# CH32V002F4U.net
KiCad netlist of a schematic drawn in Altium Designer
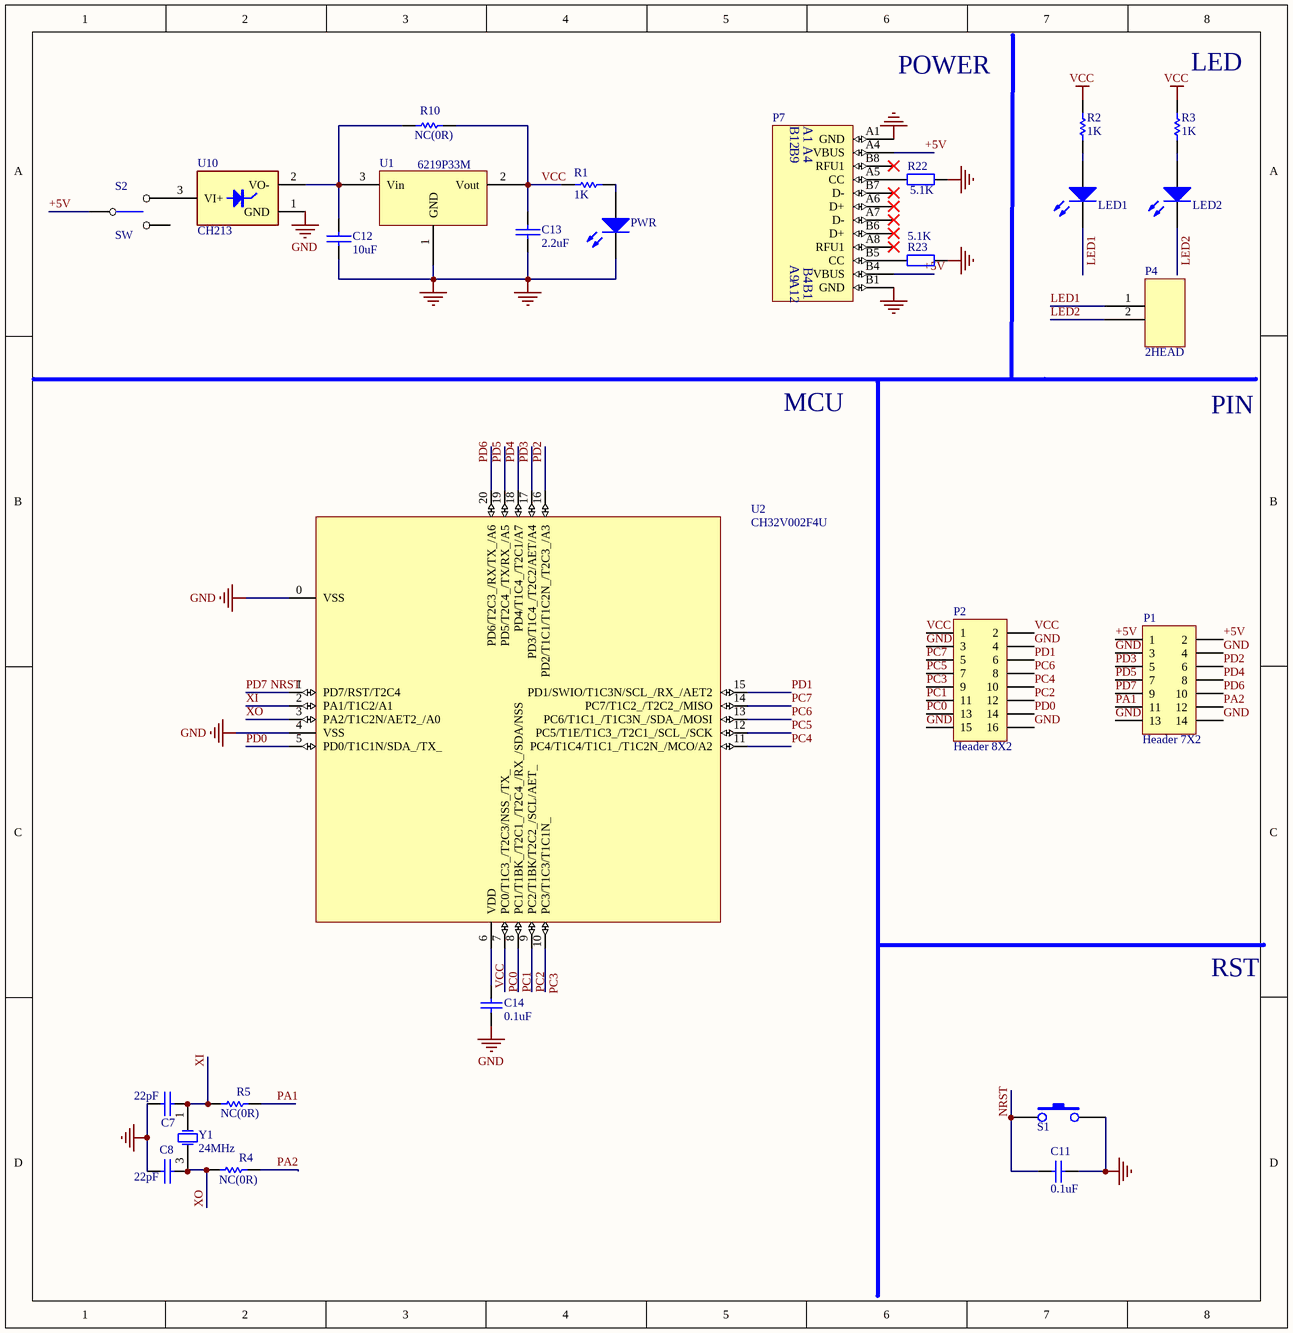
[diagram p0: CH32V002F4U.SchDoc]

(export (version "E")
  (design (tool "Eeschema 10.0.6"))
  (components
    (comp (ref "C7")
      (value "22pF")
      (footprint "0402_C")
      (description "Capacitor")
      (libsource (lib "*") (part "CAP"))
    )
    (comp (ref "C8")
      (value "22pF")
      (footprint "0402_C")
      (description "Capacitor")
      (libsource (lib "*") (part "CAP"))
    )
    (comp (ref "C11")
      (value "0.1uF")
      (footprint "0402_C")
      (description "Capacitor")
      (fields (field (name "PUBLISHER") "Altium Limited"))
      (libsource (lib "*") (part "Cap"))
    )
    (comp (ref "C12")
      (value "10uF")
      (footprint "0603_C")
      (description "Capacitor")
      (libsource (lib "wch_sch_others") (part "CAP"))
    )
    (comp (ref "C13")
      (value "2.2uF")
      (footprint "0402_C")
      (description "Capacitor")
      (libsource (lib "wch_sch_others") (part "CAP"))
    )
    (comp (ref "C14")
      (value "0.1uF")
      (footprint "0603_C")
      (description "Capacitor")
      (fields (field (name "PUBLISHER") "Altium Limited"))
      (libsource (lib "*") (part "Cap"))
    )
    (comp (ref "LED1")
      (value "LED1   blue")
      (footprint "0603+")
      (description "Typical INFRARED GaAs LED")
      (fields (field (name "PUBLISHER") "Altium Limited"))
      (libsource (lib "") (part "LED0_1"))
    )
    (comp (ref "LED2")
      (value "LED2  blue")
      (footprint "0603+")
      (description "Typical INFRARED GaAs LED")
      (fields (field (name "PUBLISHER") "Altium Limited"))
      (libsource (lib "") (part "LED0_1"))
    )
    (comp (ref "P1")
      (value "Header 7X2")
      (footprint "HDR2X7")
      (description "Header, 7-Pin, Dual row")
      (fields (field (name "PUBLISHER") "Altium Limited"))
      (libsource (lib "Miscellaneous Connectors") (part "Header 7X2"))
    )
    (comp (ref "P2")
      (value "Header 8X2")
      (footprint "HDR2X8")
      (description "Header, 8-Pin, Dual row")
      (fields (field (name "PUBLISHER") "Altium Limited"))
      (libsource (lib "Miscellaneous Connectors") (part "Header 8X2"))
    )
    (comp (ref "P4") (value "2HEAD") (footprint "SIP2-2.54mm") (libsource (lib "*") (part "2HEAD")))
    (comp (ref "P7")
      (value "TYPE-C")
      (footprint "TYPE-C-Receptacle-2.0")
      (libsource (lib "*") (part "TYPE-C1"))
    )
    (comp (ref "PWR")
      (value "POWER  red")
      (footprint "0603+")
      (description "Typical INFRARED GaAs LED")
      (fields (field (name "PUBLISHER") "Altium Limited"))
      (libsource (lib "*") (part "LED0"))
    )
    (comp (ref "R1")
      (value "1K")
      (footprint "0402")
      (description "Semiconductor Resistor")
      (fields (field (name "PUBLISHER") "Altium Limited"))
      (libsource (lib "*") (part "Res Semi"))
    )
    (comp (ref "R2")
      (value "1K")
      (footprint "0402")
      (description "Semiconductor Resistor")
      (fields (field (name "PUBLISHER") "Altium Limited"))
      (libsource (lib "*") (part "Res Semi"))
    )
    (comp (ref "R3")
      (value "1K")
      (footprint "0402")
      (description "Semiconductor Resistor")
      (fields (field (name "PUBLISHER") "Altium Limited"))
      (libsource (lib "*") (part "Res Semi"))
    )
    (comp (ref "R4")
      (value "NC(0R)")
      (footprint "0402")
      (description "Semiconductor Resistor")
      (fields (field (name "Comment") "0R") (field (name "PUBLISHER") "Altium Limited"))
      (libsource (lib "*") (part "Res Semi"))
    )
    (comp (ref "R5")
      (value "NC(0R)")
      (footprint "0402")
      (description "Semiconductor Resistor")
      (fields (field (name "Comment") "0R") (field (name "PUBLISHER") "Altium Limited"))
      (libsource (lib "*") (part "Res Semi"))
    )
    (comp (ref "R10")
      (value "NC(0R)")
      (footprint "0402")
      (description "Semiconductor Resistor")
      (fields (field (name "Comment") "0R") (field (name "PUBLISHER") "Altium Limited"))
      (libsource (lib "*") (part "Res Semi"))
    )
    (comp (ref "R22")
      (value "5.1K")
      (footprint "0402")
      (description "Resistor")
      (libsource (lib "Miscellaneous Devices") (part "Res2"))
    )
    (comp (ref "R23")
      (value "5.1K")
      (footprint "0402")
      (description "Resistor")
      (libsource (lib "Miscellaneous Devices") (part "Res2"))
    )
    (comp (ref "S1") (value "NRST") (footprint "SMD_6.1x3.65x2.5mm-KEY") (libsource (lib "*") (part "KEY")))
    (comp (ref "S2") (value "SW") (footprint "SW1") (libsource (lib "*") (part "SW")))
    (comp (ref "U1")
      (value "6219P33M")
      (footprint "SOT-23")
      (libsource (lib "wch_sch_others") (part "6219P33M"))
    )
    (comp (ref "U2")
      (value "CH32V002F4U")
      (footprint "QFN20_3X3")
      (description "RISC-V MCU, 48MHz, ADC/UART/I2C/SPI")
      (libsource (lib "DHXXXSCH") (part "CH32V002F4U6"))
    )
    (comp (ref "U10")
      (value "CH213")
      (footprint "SOT-23-3")
      (description "Ideal Diode 5V*1A")
      (libsource (lib "CHXXX") (part "CH213E"))
    )
    (comp (ref "Y1")
      (value "24MHz")
      (footprint "XT3225")
      (description "Crystal Oscillator")
      (fields (field (name "PUBLISHER") "Altium Limited"))
      (libsource (lib "*") (part "XTAL"))
    )
  )
  (nets
    (net (code "1") (name "/+5V") (class "Default")
      (node (ref "P1") (pin "1") (pinfunction "1_1") (pintype "passive"))
      (node (ref "P1") (pin "2") (pinfunction "2_2") (pintype "passive"))
      (node (ref "P7") (pin "A4") (pinfunction "VBUS_A4") (pintype "bidirectional"))
      (node (ref "P7") (pin "B4") (pinfunction "VBUS_B4") (pintype "bidirectional"))
      (node (ref "S2") (pin "1") (pinfunction "1_1") (pintype "passive"))
    )
    (net (code "2") (name "/LED1") (class "Default")
      (node (ref "LED1") (pin "2") (pinfunction "K_2") (pintype "passive"))
      (node (ref "P4") (pin "1") (pintype "passive"))
    )
    (net (code "3") (name "/LED2") (class "Default")
      (node (ref "LED2") (pin "2") (pinfunction "K_2") (pintype "passive"))
      (node (ref "P4") (pin "2") (pintype "passive"))
    )
    (net (code "4") (name "/NRST") (class "Default")
      (node (ref "C11") (pin "2") (pinfunction "2_2") (pintype "passive"))
      (node (ref "P1") (pin "9") (pinfunction "9_9") (pintype "passive"))
      (node (ref "S1") (pin "1") (pinfunction "1_1") (pintype "passive"))
      (node (ref "U2") (pin "1") (pinfunction "PD7/RST/T2C4_1") (pintype "bidirectional"))
    )
    (net (code "5") (name "/PA1") (class "Default")
      (node (ref "P1") (pin "11") (pinfunction "11_11") (pintype "passive"))
      (node (ref "R5") (pin "2") (pinfunction "2_2") (pintype "passive"))
    )
    (net (code "6") (name "/PA2") (class "Default")
      (node (ref "P1") (pin "12") (pinfunction "12_12") (pintype "passive"))
      (node (ref "R4") (pin "2") (pinfunction "2_2") (pintype "passive"))
    )
    (net (code "7") (name "/PC0") (class "Default")
      (node (ref "P2") (pin "13") (pinfunction "13_13") (pintype "passive"))
      (node (ref "U2") (pin "7") (pinfunction "PC0/T1C3_/T2C3/NSS_/TX__7") (pintype "bidirectional"))
    )
    (net (code "8") (name "/PC1") (class "Default")
      (node (ref "P2") (pin "11") (pinfunction "11_11") (pintype "passive"))
      (node (ref "U2") (pin "8") (pinfunction "PC1/T1BK_/T2C1_/T2C4_/RX_/SDA/NSS_8") (pintype "bidirectional"))
    )
    (net (code "9") (name "/PC2") (class "Default")
      (node (ref "P2") (pin "12") (pinfunction "12_12") (pintype "passive"))
      (node (ref "U2") (pin "9") (pinfunction "PC2/T1BK/T2C2_/SCL/AET__9") (pintype "bidirectional"))
    )
    (net (code "10") (name "/PC3") (class "Default")
      (node (ref "P2") (pin "9") (pinfunction "9_9") (pintype "passive"))
      (node (ref "U2") (pin "10") (pinfunction "PC3/T1C3/T1C1N__10") (pintype "bidirectional"))
    )
    (net (code "11") (name "/PC4") (class "Default")
      (node (ref "P2") (pin "10") (pinfunction "10_10") (pintype "passive"))
      (node (ref "U2") (pin "11") (pinfunction "PC4/T1C4/T1C1_/T1C2N_/MCO/A2_11") (pintype "bidirectional"))
    )
    (net (code "12") (name "/PC5") (class "Default")
      (node (ref "P2") (pin "7") (pinfunction "7_7") (pintype "passive"))
      (node (ref "U2") (pin "12") (pinfunction "PC5/T1E/T1C3_/T2C1_/SCL_/SCK_12") (pintype "bidirectional"))
    )
    (net (code "13") (name "/PC6") (class "Default")
      (node (ref "P2") (pin "8") (pinfunction "8_8") (pintype "passive"))
      (node (ref "U2") (pin "13") (pinfunction "PC6/T1C1_/T1C3N_/SDA_/MOSI_13") (pintype "bidirectional"))
    )
    (net (code "14") (name "/PC7") (class "Default")
      (node (ref "P2") (pin "5") (pinfunction "5_5") (pintype "passive"))
      (node (ref "U2") (pin "14") (pinfunction "PC7/T1C2_/T2C2_/MISO_14") (pintype "bidirectional"))
    )
    (net (code "15") (name "/PD0") (class "Default")
      (node (ref "P2") (pin "14") (pinfunction "14_14") (pintype "passive"))
      (node (ref "U2") (pin "5") (pinfunction "PD0/T1C1N/SDA_/TX__5") (pintype "bidirectional"))
    )
    (net (code "16") (name "/PD1") (class "Default")
      (node (ref "P2") (pin "6") (pinfunction "6_6") (pintype "passive"))
      (node (ref "U2") (pin "15") (pinfunction "PD1/SWIO/T1C3N/SCL_/RX_/AET2_15") (pintype "bidirectional"))
    )
    (net (code "17") (name "/PD2") (class "Default")
      (node (ref "P1") (pin "6") (pinfunction "6_6") (pintype "passive"))
      (node (ref "U2") (pin "16") (pinfunction "PD2/T1C1/T1C2N_/T2C3_/A3_16") (pintype "bidirectional"))
    )
    (net (code "18") (name "/PD3") (class "Default")
      (node (ref "P1") (pin "5") (pinfunction "5_5") (pintype "passive"))
      (node (ref "U2") (pin "17") (pinfunction "PD3/T1C4_/T2C2/AET/A4_17") (pintype "bidirectional"))
    )
    (net (code "19") (name "/PD4") (class "Default")
      (node (ref "P1") (pin "8") (pinfunction "8_8") (pintype "passive"))
      (node (ref "U2") (pin "18") (pinfunction "PD4/T1C4_/T2C1/A7_18") (pintype "bidirectional"))
    )
    (net (code "20") (name "/PD5") (class "Default")
      (node (ref "P1") (pin "7") (pinfunction "7_7") (pintype "passive"))
      (node (ref "U2") (pin "19") (pinfunction "PD5/T2C4_/TX/RX_/A5_19") (pintype "bidirectional"))
    )
    (net (code "21") (name "/PD6") (class "Default")
      (node (ref "P1") (pin "10") (pinfunction "10_10") (pintype "passive"))
      (node (ref "U2") (pin "20") (pinfunction "PD6/T2C3_/RX/TX_/A6_20") (pintype "bidirectional"))
    )
    (net (code "22") (name "/XI") (class "Default")
      (node (ref "C7") (pin "2") (pinfunction "2_2") (pintype "passive"))
      (node (ref "R5") (pin "1") (pinfunction "1_1") (pintype "passive"))
      (node (ref "U2") (pin "2") (pinfunction "PA1/T1C2/A1_2") (pintype "bidirectional"))
      (node (ref "Y1") (pin "1") (pinfunction "OSC1_1") (pintype "passive"))
    )
    (net (code "23") (name "/XO") (class "Default")
      (node (ref "C8") (pin "2") (pinfunction "2_2") (pintype "passive"))
      (node (ref "R4") (pin "1") (pinfunction "1_1") (pintype "passive"))
      (node (ref "U2") (pin "3") (pinfunction "PA2/T1C2N/AET2_/A0_3") (pintype "bidirectional"))
      (node (ref "Y1") (pin "3") (pinfunction "OSC2_3") (pintype "passive"))
    )
    (net (code "24") (name "GND") (class "Default")
      (node (ref "C11") (pin "1") (pinfunction "1_1") (pintype "passive"))
      (node (ref "C12") (pin "2") (pinfunction "2_2") (pintype "passive"))
      (node (ref "C13") (pin "1") (pinfunction "1_1") (pintype "passive"))
      (node (ref "C14") (pin "2") (pinfunction "2_2") (pintype "passive"))
      (node (ref "C7") (pin "1") (pinfunction "1_1") (pintype "passive"))
      (node (ref "C8") (pin "1") (pinfunction "1_1") (pintype "passive"))
      (node (ref "P1") (pin "13") (pinfunction "13_13") (pintype "passive"))
      (node (ref "P1") (pin "14") (pinfunction "14_14") (pintype "passive"))
      (node (ref "P1") (pin "3") (pinfunction "3_3") (pintype "passive"))
      (node (ref "P1") (pin "4") (pinfunction "4_4") (pintype "passive"))
      (node (ref "P2") (pin "15") (pinfunction "15_15") (pintype "passive"))
      (node (ref "P2") (pin "16") (pinfunction "16_16") (pintype "passive"))
      (node (ref "P2") (pin "3") (pinfunction "3_3") (pintype "passive"))
      (node (ref "P2") (pin "4") (pinfunction "4_4") (pintype "passive"))
      (node (ref "P7") (pin "A1") (pinfunction "GND_A1") (pintype "bidirectional"))
      (node (ref "P7") (pin "B1") (pinfunction "GND_B1") (pintype "bidirectional"))
      (node (ref "PWR") (pin "2") (pinfunction "K_2") (pintype "passive"))
      (node (ref "R22") (pin "2") (pinfunction "2_2") (pintype "passive"))
      (node (ref "R23") (pin "2") (pinfunction "2_2") (pintype "passive"))
      (node (ref "S1") (pin "2") (pinfunction "2_2") (pintype "passive"))
      (node (ref "U1") (pin "1") (pinfunction "GND_1") (pintype "passive"))
      (node (ref "U10") (pin "1") (pinfunction "GND_1") (pintype "power_in"))
      (node (ref "U2") (pin "0") (pinfunction "VSS_0") (pintype "power_in"))
      (node (ref "U2") (pin "4") (pinfunction "VSS_4") (pintype "power_in"))
    )
    (net (code "25") (name "Net-(LED1-A)") (class "Default")
      (node (ref "LED1") (pin "1") (pinfunction "A_1") (pintype "passive"))
      (node (ref "R2") (pin "2") (pinfunction "2_2") (pintype "passive"))
    )
    (net (code "26") (name "Net-(LED2-A)") (class "Default")
      (node (ref "LED2") (pin "1") (pinfunction "A_1") (pintype "passive"))
      (node (ref "R3") (pin "2") (pinfunction "2_2") (pintype "passive"))
    )
    (net (code "27") (name "Net-(P7-CC-PadA5)") (class "Default")
      (node (ref "P7") (pin "A5") (pinfunction "CC_A5") (pintype "bidirectional"))
      (node (ref "R22") (pin "1") (pinfunction "1_1") (pintype "passive"))
    )
    (net (code "28") (name "Net-(P7-CC-PadB5)") (class "Default")
      (node (ref "P7") (pin "B5") (pinfunction "CC_B5") (pintype "bidirectional"))
      (node (ref "R23") (pin "1") (pinfunction "1_1") (pintype "passive"))
    )
    (net (code "29") (name "Net-(PWR-A)") (class "Default")
      (node (ref "PWR") (pin "1") (pinfunction "A_1") (pintype "passive"))
      (node (ref "R1") (pin "1") (pinfunction "1_1") (pintype "passive"))
    )
    (net (code "30") (name "Net-(U1-Vin)") (class "Default")
      (node (ref "C12") (pin "1") (pinfunction "1_1") (pintype "passive"))
      (node (ref "R10") (pin "1") (pinfunction "1_1") (pintype "passive"))
      (node (ref "U1") (pin "3") (pinfunction "Vin_3") (pintype "passive"))
      (node (ref "U10") (pin "2") (pinfunction "VO-_2") (pintype "power_in"))
    )
    (net (code "31") (name "Net-(U10-VI+)") (class "Default")
      (node (ref "S2") (pin "3") (pinfunction "3_3") (pintype "passive"))
      (node (ref "U10") (pin "3") (pinfunction "VI+_3") (pintype "power_in"))
    )
    (net (code "32") (name "VCC") (class "Default")
      (node (ref "C13") (pin "2") (pinfunction "2_2") (pintype "passive"))
      (node (ref "C14") (pin "1") (pinfunction "1_1") (pintype "passive"))
      (node (ref "P2") (pin "1") (pinfunction "1_1") (pintype "passive"))
      (node (ref "P2") (pin "2") (pinfunction "2_2") (pintype "passive"))
      (node (ref "R1") (pin "2") (pinfunction "2_2") (pintype "passive"))
      (node (ref "R10") (pin "2") (pinfunction "2_2") (pintype "passive"))
      (node (ref "R2") (pin "1") (pinfunction "1_1") (pintype "passive"))
      (node (ref "R3") (pin "1") (pinfunction "1_1") (pintype "passive"))
      (node (ref "U1") (pin "2") (pinfunction "Vout_2") (pintype "passive"))
      (node (ref "U2") (pin "6") (pinfunction "VDD_6") (pintype "power_in"))
    )
    (net (code "33") (name "unconnected-(P7-D+-PadA6)") (class "Default")
      (node (ref "P7") (pin "A6") (pinfunction "D+_A6") (pintype "bidirectional+no_connect"))
    )
    (net (code "34") (name "unconnected-(P7-D+-PadB6)") (class "Default")
      (node (ref "P7") (pin "B6") (pinfunction "D+_B6") (pintype "bidirectional+no_connect"))
    )
    (net (code "35") (name "unconnected-(P7-D--PadA7)") (class "Default")
      (node (ref "P7") (pin "A7") (pinfunction "D-_A7") (pintype "bidirectional+no_connect"))
    )
    (net (code "36") (name "unconnected-(P7-D--PadB7)") (class "Default")
      (node (ref "P7") (pin "B7") (pinfunction "D-_B7") (pintype "bidirectional+no_connect"))
    )
    (net (code "37") (name "unconnected-(P7-RFU1-PadA8)") (class "Default")
      (node (ref "P7") (pin "A8") (pinfunction "RFU1_A8") (pintype "bidirectional+no_connect"))
    )
    (net (code "38") (name "unconnected-(P7-RFU1-PadB8)") (class "Default")
      (node (ref "P7") (pin "B8") (pinfunction "RFU1_B8") (pintype "bidirectional+no_connect"))
    )
    (net (code "39") (name "unconnected-(S2-Pad2)") (class "Default")
      (node (ref "S2") (pin "2") (pinfunction "2_2") (pintype "passive"))
    )
  )
)
